# PreAmp.net
KiCad netlist of a schematic drawn in Altium Designer
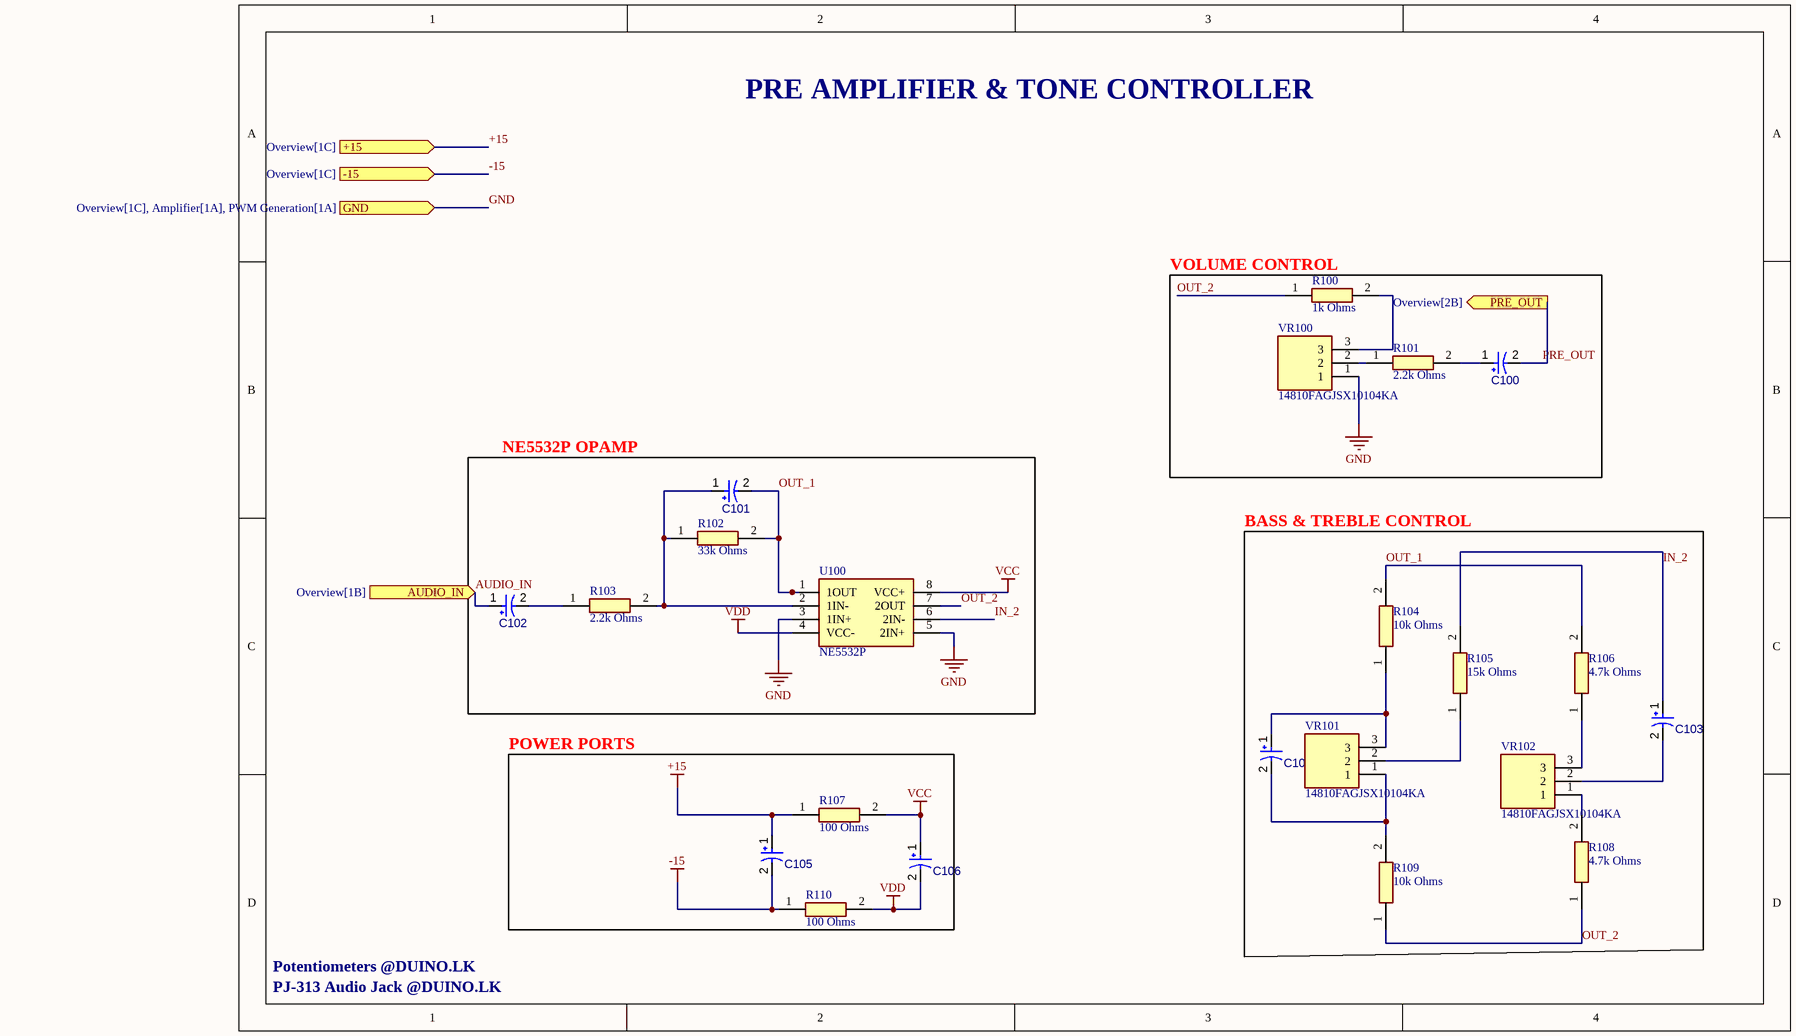
[diagram p0: PreAmp.SchDoc]

(export (version "E")
  (design (tool "Eeschema 10.0.6"))
  (components
    (comp (ref "C100")
      (value "10uF")
      (footprint "CAPPR65-500-1600X1000X1700")
      (fields (field (name "TOLERANCE") "20%") (field (name "MANUFACTURER") "Panasonic"))
      (libsource (lib "Rahulb 23") (part "CAP-P-2"))
    )
    (comp (ref "C101")
      (value "47pF")
      (footprint "CAPPR65-500-1600X1000X1700")
      (fields (field (name "TOLERANCE") "20%") (field (name "MANUFACTURER") "Panasonic"))
      (libsource (lib "Rahulb 23") (part "CAP-P-2"))
    )
    (comp (ref "C102")
      (value "10uF")
      (footprint "CAPPR65-500-1600X1000X1700")
      (fields (field (name "TOLERANCE") "20%") (field (name "MANUFACTURER") "Panasonic"))
      (libsource (lib "Rahulb 23") (part "CAP-P-2"))
    )
    (comp (ref "C103")
      (value "2.2nF")
      (footprint "CAPPR65-500-1600X1000X1700")
      (fields (field (name "TOLERANCE") "20%") (field (name "MANUFACTURER") "Panasonic"))
      (libsource (lib "") (part "CAP-P-2_1"))
    )
    (comp (ref "C104")
      (value "47nF")
      (footprint "CAPPR65-500-1600X1000X1700")
      (fields (field (name "TOLERANCE") "20%") (field (name "MANUFACTURER") "Panasonic"))
      (libsource (lib "") (part "CAP-P-2_1"))
    )
    (comp (ref "C105")
      (value "1000uF")
      (footprint "CAPPR65-500-1600X1000X1700")
      (fields (field (name "TOLERANCE") "20%") (field (name "MANUFACTURER") "Panasonic"))
      (libsource (lib "") (part "CAP-P-2_1"))
    )
    (comp (ref "C106")
      (value "100nF")
      (footprint "CAPPR65-500-1600X1000X1700")
      (fields (field (name "TOLERANCE") "20%") (field (name "MANUFACTURER") "Panasonic"))
      (libsource (lib "") (part "CAP-P-2_1"))
    )
    (comp (ref "R100")
      (value "1k Ohms")
      (footprint "RESAD1650W60L650D250")
      (description "Resistor")
      (fields
        (field (name "MANUFACTURER_PART_NUMBER") "MRS25000C1052FCT00")
        (field (name "MOUSER PART NUMBER") "594-MRS25000C1052FCT")
      )
      (libsource (lib "Schlib1") (part "MRS25000C1052FCT00"))
    )
    (comp (ref "R101")
      (value "2.2k Ohms")
      (footprint "RESAD1650W60L650D250")
      (description "Resistor")
      (fields
        (field (name "MANUFACTURER_PART_NUMBER") "MRS25000C1052FCT00")
        (field (name "MOUSER PART NUMBER") "594-MRS25000C1052FCT")
      )
      (libsource (lib "Schlib1") (part "MRS25000C1052FCT00"))
    )
    (comp (ref "R102")
      (value "33k Ohms")
      (footprint "RESAD1650W60L650D250")
      (description "Resistor")
      (fields
        (field (name "MANUFACTURER_PART_NUMBER") "MRS25000C1052FCT00")
        (field (name "MOUSER PART NUMBER") "594-MRS25000C1052FCT")
      )
      (libsource (lib "Schlib1") (part "MRS25000C1052FCT00"))
    )
    (comp (ref "R103")
      (value "2.2k Ohms")
      (footprint "RESAD1650W60L650D250")
      (description "Resistor")
      (fields
        (field (name "MANUFACTURER_PART_NUMBER") "MRS25000C1052FCT00")
        (field (name "MOUSER PART NUMBER") "594-MRS25000C1052FCT")
      )
      (libsource (lib "Schlib1") (part "MRS25000C1052FCT00"))
    )
    (comp (ref "R104")
      (value "10k Ohms")
      (footprint "RESAD1650W60L650D250")
      (description "Resistor")
      (fields
        (field (name "MANUFACTURER_PART_NUMBER") "MRS25000C1052FCT00")
        (field (name "MOUSER PART NUMBER") "594-MRS25000C1052FCT")
      )
      (libsource (lib "") (part "MRS25000C1052FCT00_1"))
    )
    (comp (ref "R105")
      (value "15k Ohms")
      (footprint "RESAD1650W60L650D250")
      (description "Resistor")
      (fields
        (field (name "MANUFACTURER_PART_NUMBER") "MRS25000C1052FCT00")
        (field (name "MOUSER PART NUMBER") "594-MRS25000C1052FCT")
      )
      (libsource (lib "") (part "MRS25000C1052FCT00_1"))
    )
    (comp (ref "R106")
      (value "4.7k Ohms")
      (footprint "RESAD1650W60L650D250")
      (description "Resistor")
      (fields
        (field (name "MANUFACTURER_PART_NUMBER") "MRS25000C1052FCT00")
        (field (name "MOUSER PART NUMBER") "594-MRS25000C1052FCT")
      )
      (libsource (lib "") (part "MRS25000C1052FCT00_1"))
    )
    (comp (ref "R107")
      (value "100 Ohms")
      (footprint "RESAD1650W60L650D250")
      (description "Resistor")
      (fields
        (field (name "MANUFACTURER_PART_NUMBER") "MRS25000C1052FCT00")
        (field (name "MOUSER PART NUMBER") "594-MRS25000C1052FCT")
      )
      (libsource (lib "Schlib1") (part "MRS25000C1052FCT00"))
    )
    (comp (ref "R108")
      (value "4.7k Ohms")
      (footprint "RESAD1650W60L650D250")
      (description "Resistor")
      (fields
        (field (name "MANUFACTURER_PART_NUMBER") "MRS25000C1052FCT00")
        (field (name "MOUSER PART NUMBER") "594-MRS25000C1052FCT")
      )
      (libsource (lib "") (part "MRS25000C1052FCT00_1"))
    )
    (comp (ref "R109")
      (value "10k Ohms")
      (footprint "RESAD1650W60L650D250")
      (description "Resistor")
      (fields
        (field (name "MANUFACTURER_PART_NUMBER") "MRS25000C1052FCT00")
        (field (name "MOUSER PART NUMBER") "594-MRS25000C1052FCT")
      )
      (libsource (lib "") (part "MRS25000C1052FCT00_1"))
    )
    (comp (ref "R110")
      (value "100 Ohms")
      (footprint "RESAD1650W60L650D250")
      (description "Resistor")
      (fields
        (field (name "MANUFACTURER_PART_NUMBER") "MRS25000C1052FCT00")
        (field (name "MOUSER PART NUMBER") "594-MRS25000C1052FCT")
      )
      (libsource (lib "Schlib1") (part "MRS25000C1052FCT00"))
    )
    (comp (ref "U100")
      (value "NE5532P")
      (footprint "DIP794W53P254L959H508Q8N")
      (description "Integrated Circuit")
      (fields (field (name "MOUSER PART NUMBER") "595-NE5532P"))
      (libsource (lib "Schlib1") (part "NE5532P"))
    )
    (comp (ref "VR100")
      (value "14810FAGJSX10104KA")
      (footprint "14810FAGJSX10104KA")
      (description "Variable Resistor")
      (fields (field (name "MOUSER PART NUMBER") "594-148-7104"))
      (libsource (lib "Schlib1") (part "14810FAGJSX10104KA"))
    )
    (comp (ref "VR101")
      (value "14810FAGJSX10104KA")
      (footprint "14810FAGJSX10104KA")
      (description "Variable Resistor")
      (fields (field (name "MOUSER PART NUMBER") "594-148-7104"))
      (libsource (lib "Schlib1") (part "14810FAGJSX10104KA"))
    )
    (comp (ref "VR102")
      (value "14810FAGJSX10104KA")
      (footprint "14810FAGJSX10104KA")
      (description "Variable Resistor")
      (fields (field (name "MOUSER PART NUMBER") "594-148-7104"))
      (libsource (lib "Schlib1") (part "14810FAGJSX10104KA"))
    )
  )
  (nets
    (net (code "1") (name "+15") (class "Default")
      (node (ref "C105") (pin "1") (pinfunction "1_1") (pintype "passive"))
      (node (ref "R107") (pin "1") (pinfunction "1_1") (pintype "passive"))
    )
    (net (code "2") (name "-15") (class "Default")
      (node (ref "C105") (pin "2") (pinfunction "2_2") (pintype "passive"))
      (node (ref "R110") (pin "1") (pinfunction "1_1") (pintype "passive"))
    )
    (net (code "3") (name "/AUDIO_IN") (class "Default")
      (node (ref "C102") (pin "1") (pinfunction "1_1") (pintype "passive"))
    )
    (net (code "4") (name "/IN_2") (class "Default")
      (node (ref "C103") (pin "1") (pinfunction "1_1") (pintype "passive"))
      (node (ref "R105") (pin "2") (pinfunction "2_2") (pintype "passive"))
      (node (ref "U100") (pin "6") (pinfunction "2IN-_6") (pintype "passive"))
    )
    (net (code "5") (name "/OUT_1") (class "Default")
      (node (ref "C101") (pin "2") (pinfunction "2_2") (pintype "passive"))
      (node (ref "R102") (pin "2") (pinfunction "2_2") (pintype "passive"))
      (node (ref "R104") (pin "2") (pinfunction "2_2") (pintype "passive"))
      (node (ref "R106") (pin "2") (pinfunction "2_2") (pintype "passive"))
      (node (ref "U100") (pin "1") (pinfunction "1OUT_1") (pintype "passive"))
    )
    (net (code "6") (name "/OUT_2") (class "Default")
      (node (ref "R100") (pin "1") (pinfunction "1_1") (pintype "passive"))
      (node (ref "R108") (pin "1") (pinfunction "1_1") (pintype "passive"))
      (node (ref "R109") (pin "1") (pinfunction "1_1") (pintype "passive"))
      (node (ref "U100") (pin "7") (pinfunction "2OUT_7") (pintype "passive"))
    )
    (net (code "7") (name "/PRE_OUT") (class "Default")
      (node (ref "C100") (pin "2") (pinfunction "2_2") (pintype "passive"))
    )
    (net (code "8") (name "GND") (class "Default")
      (node (ref "U100") (pin "3") (pinfunction "1IN+_3") (pintype "passive"))
      (node (ref "U100") (pin "5") (pinfunction "2IN+_5") (pintype "passive"))
      (node (ref "VR100") (pin "1") (pinfunction "1_1") (pintype "passive"))
    )
    (net (code "9") (name "Net-(C100-Pad1)") (class "Default")
      (node (ref "C100") (pin "1") (pinfunction "1_1") (pintype "passive"))
      (node (ref "R101") (pin "2") (pinfunction "2_2") (pintype "passive"))
    )
    (net (code "10") (name "Net-(C102-Pad2)") (class "Default")
      (node (ref "C102") (pin "2") (pinfunction "2_2") (pintype "passive"))
      (node (ref "R103") (pin "1") (pinfunction "1_1") (pintype "passive"))
    )
    (net (code "11") (name "Net-(C103-Pad2)") (class "Default")
      (node (ref "C103") (pin "2") (pinfunction "2_2") (pintype "passive"))
      (node (ref "VR102") (pin "2") (pinfunction "2_2") (pintype "passive"))
    )
    (net (code "12") (name "Net-(C104-Pad1)") (class "Default")
      (node (ref "C104") (pin "1") (pinfunction "1_1") (pintype "passive"))
      (node (ref "R104") (pin "1") (pinfunction "1_1") (pintype "passive"))
      (node (ref "VR101") (pin "3") (pinfunction "3_3") (pintype "passive"))
    )
    (net (code "13") (name "Net-(C104-Pad2)") (class "Default")
      (node (ref "C104") (pin "2") (pinfunction "2_2") (pintype "passive"))
      (node (ref "R109") (pin "2") (pinfunction "2_2") (pintype "passive"))
      (node (ref "VR101") (pin "1") (pinfunction "1_1") (pintype "passive"))
    )
    (net (code "14") (name "Net-(R100-Pad2)") (class "Default")
      (node (ref "R100") (pin "2") (pinfunction "2_2") (pintype "passive"))
      (node (ref "VR100") (pin "3") (pinfunction "3_3") (pintype "passive"))
    )
    (net (code "15") (name "Net-(R101-Pad1)") (class "Default")
      (node (ref "R101") (pin "1") (pinfunction "1_1") (pintype "passive"))
      (node (ref "VR100") (pin "2") (pinfunction "2_2") (pintype "passive"))
    )
    (net (code "16") (name "Net-(R105-Pad1)") (class "Default")
      (node (ref "R105") (pin "1") (pinfunction "1_1") (pintype "passive"))
      (node (ref "VR101") (pin "2") (pinfunction "2_2") (pintype "passive"))
    )
    (net (code "17") (name "Net-(R106-Pad1)") (class "Default")
      (node (ref "R106") (pin "1") (pinfunction "1_1") (pintype "passive"))
      (node (ref "VR102") (pin "3") (pinfunction "3_3") (pintype "passive"))
    )
    (net (code "18") (name "Net-(R108-Pad2)") (class "Default")
      (node (ref "R108") (pin "2") (pinfunction "2_2") (pintype "passive"))
      (node (ref "VR102") (pin "1") (pinfunction "1_1") (pintype "passive"))
    )
    (net (code "19") (name "Net-(U100-1IN-)") (class "Default")
      (node (ref "C101") (pin "1") (pinfunction "1_1") (pintype "passive"))
      (node (ref "R102") (pin "1") (pinfunction "1_1") (pintype "passive"))
      (node (ref "R103") (pin "2") (pinfunction "2_2") (pintype "passive"))
      (node (ref "U100") (pin "2") (pinfunction "1IN-_2") (pintype "passive"))
    )
    (net (code "20") (name "VCC") (class "Default")
      (node (ref "C106") (pin "1") (pinfunction "1_1") (pintype "passive"))
      (node (ref "R107") (pin "2") (pinfunction "2_2") (pintype "passive"))
      (node (ref "U100") (pin "8") (pinfunction "VCC+_8") (pintype "passive"))
    )
    (net (code "21") (name "VDD") (class "Default")
      (node (ref "C106") (pin "2") (pinfunction "2_2") (pintype "passive"))
      (node (ref "R110") (pin "2") (pinfunction "2_2") (pintype "passive"))
      (node (ref "U100") (pin "4") (pinfunction "VCC-_4") (pintype "passive"))
    )
  )
)
